# M111D.net
KiCad netlist of a schematic drawn in EAGLE
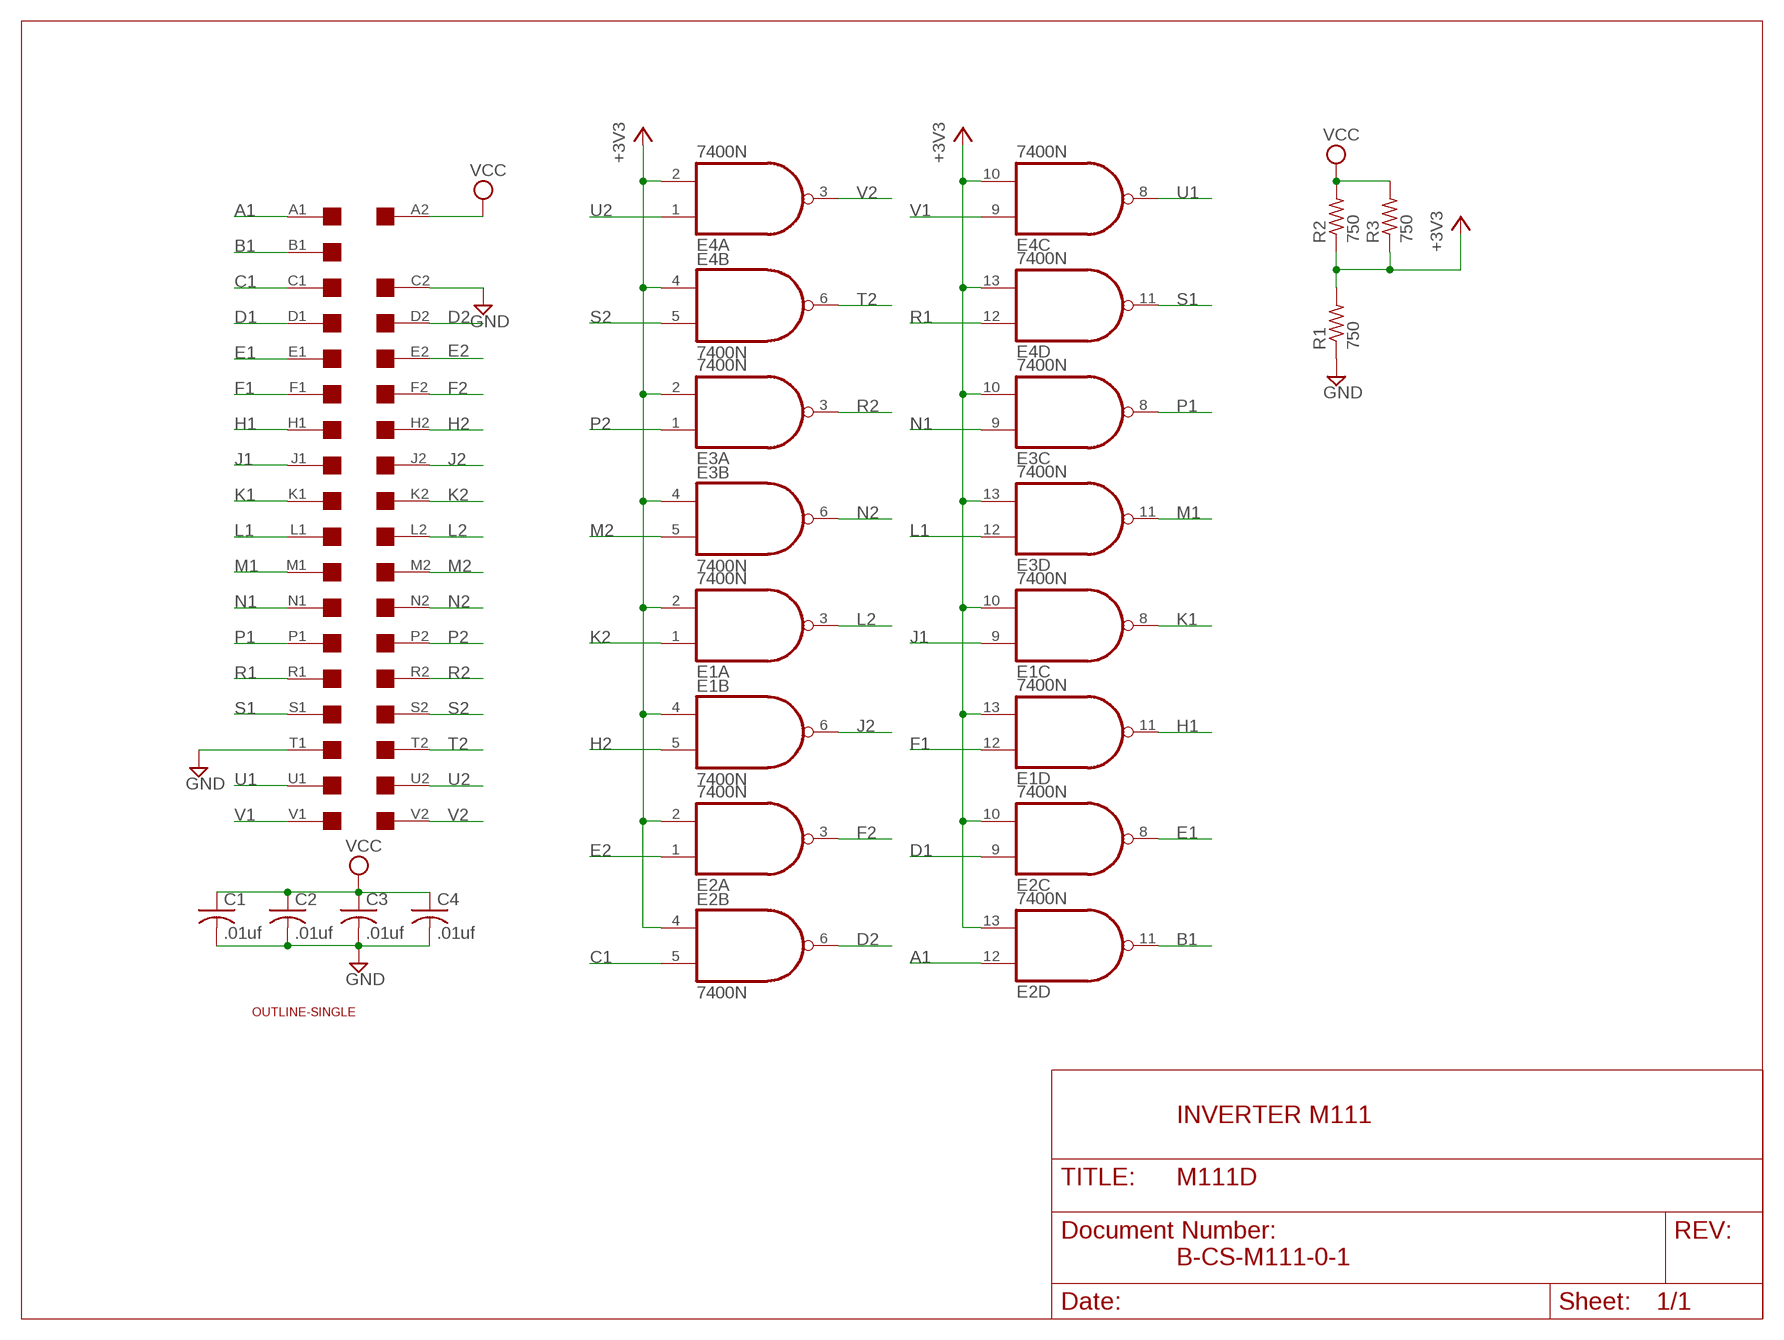
[diagram p0: schematic, sheet 1]

(export (version "E")
  (design (tool "Eeschema 10.0.6"))
  (components
    (comp (ref "A")
      (value "EDGE-2CONNECTOR")
      (footprint "eagle-import:EDGE-CON2")
      (libsource (lib "eagle-import") (part "EDGE-2CONNECTOR"))
    )
    (comp (ref "C1")
      (value ".01uf")
      (footprint "eagle-import:C050-025X075")
      (libsource (lib "eagle-import") (part "C-US050-025X075"))
    )
    (comp (ref "C2")
      (value ".01uf")
      (footprint "eagle-import:C050-025X075")
      (libsource (lib "eagle-import") (part "C-US050-025X075"))
    )
    (comp (ref "C3")
      (value ".01uf")
      (footprint "eagle-import:C050-025X075")
      (libsource (lib "eagle-import") (part "C-US050-025X075"))
    )
    (comp (ref "C4")
      (value ".01uf")
      (footprint "eagle-import:C050-025X075")
      (libsource (lib "eagle-import") (part "C-US050-025X075"))
    )
    (comp (ref "E1")
      (value "7400N")
      (footprint "eagle-import:DIL14")
      (libsource (lib "eagle-import") (part "7400N"))
    )
    (comp (ref "E2")
      (value "7400N")
      (footprint "eagle-import:DIL14")
      (libsource (lib "eagle-import") (part "7400N"))
    )
    (comp (ref "E3")
      (value "7400N")
      (footprint "eagle-import:DIL14")
      (libsource (lib "eagle-import") (part "7400N"))
    )
    (comp (ref "E4")
      (value "7400N")
      (footprint "eagle-import:DIL14")
      (libsource (lib "eagle-import") (part "7400N"))
    )
    (comp (ref "R1")
      (value "750")
      (footprint "eagle-import:0207_10")
      (libsource (lib "eagle-import") (part "R-US_0207/10"))
    )
    (comp (ref "R2")
      (value "750")
      (footprint "eagle-import:0207_10")
      (libsource (lib "eagle-import") (part "R-US_0207/10"))
    )
    (comp (ref "R3")
      (value "750")
      (footprint "eagle-import:0207_10")
      (libsource (lib "eagle-import") (part "R-US_0207/10"))
    )
    (comp (ref "U$1")
      (value "OUTLINE-SINGLE")
      (footprint "eagle-import:SINGLE")
      (libsource (lib "eagle-import") (part "OUTLINE-SINGLE"))
    )
  )
  (nets
    (net (code "1") (name "+3V3") (class "Default")
      (node (ref "E1") (pin "10") (pinfunction "I1_10") (pintype "input"))
      (node (ref "E1") (pin "13") (pinfunction "I1_13") (pintype "input"))
      (node (ref "E1") (pin "2") (pinfunction "I1_2") (pintype "input"))
      (node (ref "E1") (pin "4") (pinfunction "I0_4") (pintype "input"))
      (node (ref "E2") (pin "10") (pinfunction "I1_10") (pintype "input"))
      (node (ref "E2") (pin "13") (pinfunction "I1_13") (pintype "input"))
      (node (ref "E2") (pin "2") (pinfunction "I1_2") (pintype "input"))
      (node (ref "E2") (pin "4") (pinfunction "I0_4") (pintype "input"))
      (node (ref "E3") (pin "10") (pinfunction "I1_10") (pintype "input"))
      (node (ref "E3") (pin "13") (pinfunction "I1_13") (pintype "input"))
      (node (ref "E3") (pin "2") (pinfunction "I1_2") (pintype "input"))
      (node (ref "E3") (pin "4") (pinfunction "I0_4") (pintype "input"))
      (node (ref "E4") (pin "10") (pinfunction "I1_10") (pintype "input"))
      (node (ref "E4") (pin "13") (pinfunction "I1_13") (pintype "input"))
      (node (ref "E4") (pin "2") (pinfunction "I1_2") (pintype "input"))
      (node (ref "E4") (pin "4") (pinfunction "I0_4") (pintype "input"))
      (node (ref "R1") (pin "2") (pinfunction "2_2") (pintype "passive"))
      (node (ref "R2") (pin "1") (pinfunction "1_1") (pintype "passive"))
      (node (ref "R3") (pin "1") (pinfunction "1_1") (pintype "passive"))
    )
    (net (code "2") (name "/A1") (class "Default")
      (node (ref "A") (pin "A1") (pinfunction "1_A1") (pintype "bidirectional"))
      (node (ref "E2") (pin "12") (pinfunction "I0_12") (pintype "input"))
    )
    (net (code "3") (name "/B1") (class "Default")
      (node (ref "A") (pin "B1") (pinfunction "1_B1") (pintype "bidirectional"))
      (node (ref "E2") (pin "11") (pinfunction "O_11") (pintype "output"))
    )
    (net (code "4") (name "/C1") (class "Default")
      (node (ref "A") (pin "C1") (pinfunction "1_C1") (pintype "bidirectional"))
      (node (ref "E2") (pin "5") (pinfunction "I1_5") (pintype "input"))
    )
    (net (code "5") (name "/D1") (class "Default")
      (node (ref "A") (pin "D1") (pinfunction "1_D1") (pintype "bidirectional"))
      (node (ref "E2") (pin "9") (pinfunction "I0_9") (pintype "input"))
    )
    (net (code "6") (name "/D2") (class "Default")
      (node (ref "A") (pin "D2") (pinfunction "1_D2") (pintype "bidirectional"))
      (node (ref "E2") (pin "6") (pinfunction "O_6") (pintype "output"))
    )
    (net (code "7") (name "/E1") (class "Default")
      (node (ref "A") (pin "E1") (pinfunction "1_E1") (pintype "bidirectional"))
      (node (ref "E2") (pin "8") (pinfunction "O_8") (pintype "output"))
    )
    (net (code "8") (name "/E2") (class "Default")
      (node (ref "A") (pin "E2") (pinfunction "1_E2") (pintype "bidirectional"))
      (node (ref "E2") (pin "1") (pinfunction "I0_1") (pintype "input"))
    )
    (net (code "9") (name "/F1") (class "Default")
      (node (ref "A") (pin "F1") (pinfunction "1_F1") (pintype "bidirectional"))
      (node (ref "E1") (pin "12") (pinfunction "I0_12") (pintype "input"))
    )
    (net (code "10") (name "/F2") (class "Default")
      (node (ref "A") (pin "F2") (pinfunction "1_F2") (pintype "bidirectional"))
      (node (ref "E2") (pin "3") (pinfunction "O_3") (pintype "output"))
    )
    (net (code "11") (name "/H1") (class "Default")
      (node (ref "A") (pin "H1") (pinfunction "1_H1") (pintype "bidirectional"))
      (node (ref "E1") (pin "11") (pinfunction "O_11") (pintype "output"))
    )
    (net (code "12") (name "/H2") (class "Default")
      (node (ref "A") (pin "H2") (pinfunction "1_H2") (pintype "bidirectional"))
      (node (ref "E1") (pin "5") (pinfunction "I1_5") (pintype "input"))
    )
    (net (code "13") (name "/J1") (class "Default")
      (node (ref "A") (pin "J1") (pinfunction "1_J1") (pintype "bidirectional"))
      (node (ref "E1") (pin "9") (pinfunction "I0_9") (pintype "input"))
    )
    (net (code "14") (name "/J2") (class "Default")
      (node (ref "A") (pin "J2") (pinfunction "1_J2") (pintype "bidirectional"))
      (node (ref "E1") (pin "6") (pinfunction "O_6") (pintype "output"))
    )
    (net (code "15") (name "/K1") (class "Default")
      (node (ref "A") (pin "K1") (pinfunction "1_K1") (pintype "bidirectional"))
      (node (ref "E1") (pin "8") (pinfunction "O_8") (pintype "output"))
    )
    (net (code "16") (name "/K2") (class "Default")
      (node (ref "A") (pin "K2") (pinfunction "1_K2") (pintype "bidirectional"))
      (node (ref "E1") (pin "1") (pinfunction "I0_1") (pintype "input"))
    )
    (net (code "17") (name "/L1") (class "Default")
      (node (ref "A") (pin "L1") (pinfunction "1_L1") (pintype "bidirectional"))
      (node (ref "E3") (pin "12") (pinfunction "I0_12") (pintype "input"))
    )
    (net (code "18") (name "/L2") (class "Default")
      (node (ref "A") (pin "L2") (pinfunction "1_L2") (pintype "bidirectional"))
      (node (ref "E1") (pin "3") (pinfunction "O_3") (pintype "output"))
    )
    (net (code "19") (name "/M1") (class "Default")
      (node (ref "A") (pin "M1") (pinfunction "1_M1") (pintype "bidirectional"))
      (node (ref "E3") (pin "11") (pinfunction "O_11") (pintype "output"))
    )
    (net (code "20") (name "/M2") (class "Default")
      (node (ref "A") (pin "M2") (pinfunction "1_M2") (pintype "bidirectional"))
      (node (ref "E3") (pin "5") (pinfunction "I1_5") (pintype "input"))
    )
    (net (code "21") (name "/N1") (class "Default")
      (node (ref "A") (pin "N1") (pinfunction "1_N1") (pintype "bidirectional"))
      (node (ref "E3") (pin "9") (pinfunction "I0_9") (pintype "input"))
    )
    (net (code "22") (name "/N2") (class "Default")
      (node (ref "A") (pin "N2") (pinfunction "1_N2") (pintype "bidirectional"))
      (node (ref "E3") (pin "6") (pinfunction "O_6") (pintype "output"))
    )
    (net (code "23") (name "/P1") (class "Default")
      (node (ref "A") (pin "P1") (pinfunction "1_P1") (pintype "bidirectional"))
      (node (ref "E3") (pin "8") (pinfunction "O_8") (pintype "output"))
    )
    (net (code "24") (name "/P2") (class "Default")
      (node (ref "A") (pin "P2") (pinfunction "1_P2") (pintype "bidirectional"))
      (node (ref "E3") (pin "1") (pinfunction "I0_1") (pintype "input"))
    )
    (net (code "25") (name "/R1") (class "Default")
      (node (ref "A") (pin "R1") (pinfunction "1_R1") (pintype "bidirectional"))
      (node (ref "E4") (pin "12") (pinfunction "I0_12") (pintype "input"))
    )
    (net (code "26") (name "/R2") (class "Default")
      (node (ref "A") (pin "R2") (pinfunction "1_R2") (pintype "bidirectional"))
      (node (ref "E3") (pin "3") (pinfunction "O_3") (pintype "output"))
    )
    (net (code "27") (name "/S1") (class "Default")
      (node (ref "A") (pin "S1") (pinfunction "1_S1") (pintype "bidirectional"))
      (node (ref "E4") (pin "11") (pinfunction "O_11") (pintype "output"))
    )
    (net (code "28") (name "/S2") (class "Default")
      (node (ref "A") (pin "S2") (pinfunction "1_S2") (pintype "bidirectional"))
      (node (ref "E4") (pin "5") (pinfunction "I1_5") (pintype "input"))
    )
    (net (code "29") (name "/T2") (class "Default")
      (node (ref "A") (pin "T2") (pinfunction "1_T2") (pintype "bidirectional"))
      (node (ref "E4") (pin "6") (pinfunction "O_6") (pintype "output"))
    )
    (net (code "30") (name "/U1") (class "Default")
      (node (ref "A") (pin "U1") (pinfunction "1_U1") (pintype "bidirectional"))
      (node (ref "E4") (pin "8") (pinfunction "O_8") (pintype "output"))
    )
    (net (code "31") (name "/U2") (class "Default")
      (node (ref "A") (pin "U2") (pinfunction "1_U2") (pintype "bidirectional"))
      (node (ref "E4") (pin "1") (pinfunction "I0_1") (pintype "input"))
    )
    (net (code "32") (name "/V1") (class "Default")
      (node (ref "A") (pin "V1") (pinfunction "1_V1") (pintype "bidirectional"))
      (node (ref "E4") (pin "9") (pinfunction "I0_9") (pintype "input"))
    )
    (net (code "33") (name "/V2") (class "Default")
      (node (ref "A") (pin "V2") (pinfunction "1_V2") (pintype "bidirectional"))
      (node (ref "E4") (pin "3") (pinfunction "O_3") (pintype "output"))
    )
    (net (code "34") (name "GND") (class "Default")
      (node (ref "A") (pin "C2") (pinfunction "1_C2") (pintype "bidirectional"))
      (node (ref "A") (pin "T1") (pinfunction "1_T1") (pintype "bidirectional"))
      (node (ref "C1") (pin "2") (pinfunction "2_2") (pintype "passive"))
      (node (ref "C2") (pin "2") (pinfunction "2_2") (pintype "passive"))
      (node (ref "C3") (pin "2") (pinfunction "2_2") (pintype "passive"))
      (node (ref "C4") (pin "2") (pinfunction "2_2") (pintype "passive"))
      (node (ref "R1") (pin "1") (pinfunction "1_1") (pintype "passive"))
    )
    (net (code "35") (name "VCC") (class "Default")
      (node (ref "A") (pin "A2") (pinfunction "1_A2") (pintype "bidirectional"))
      (node (ref "C1") (pin "1") (pinfunction "1_1") (pintype "passive"))
      (node (ref "C2") (pin "1") (pinfunction "1_1") (pintype "passive"))
      (node (ref "C3") (pin "1") (pinfunction "1_1") (pintype "passive"))
      (node (ref "C4") (pin "1") (pinfunction "1_1") (pintype "passive"))
      (node (ref "R2") (pin "2") (pinfunction "2_2") (pintype "passive"))
      (node (ref "R3") (pin "2") (pinfunction "2_2") (pintype "passive"))
    )
  )
)
